# Ethernet_Besturing.net
KiCad netlist of a schematic drawn in EasyEDA
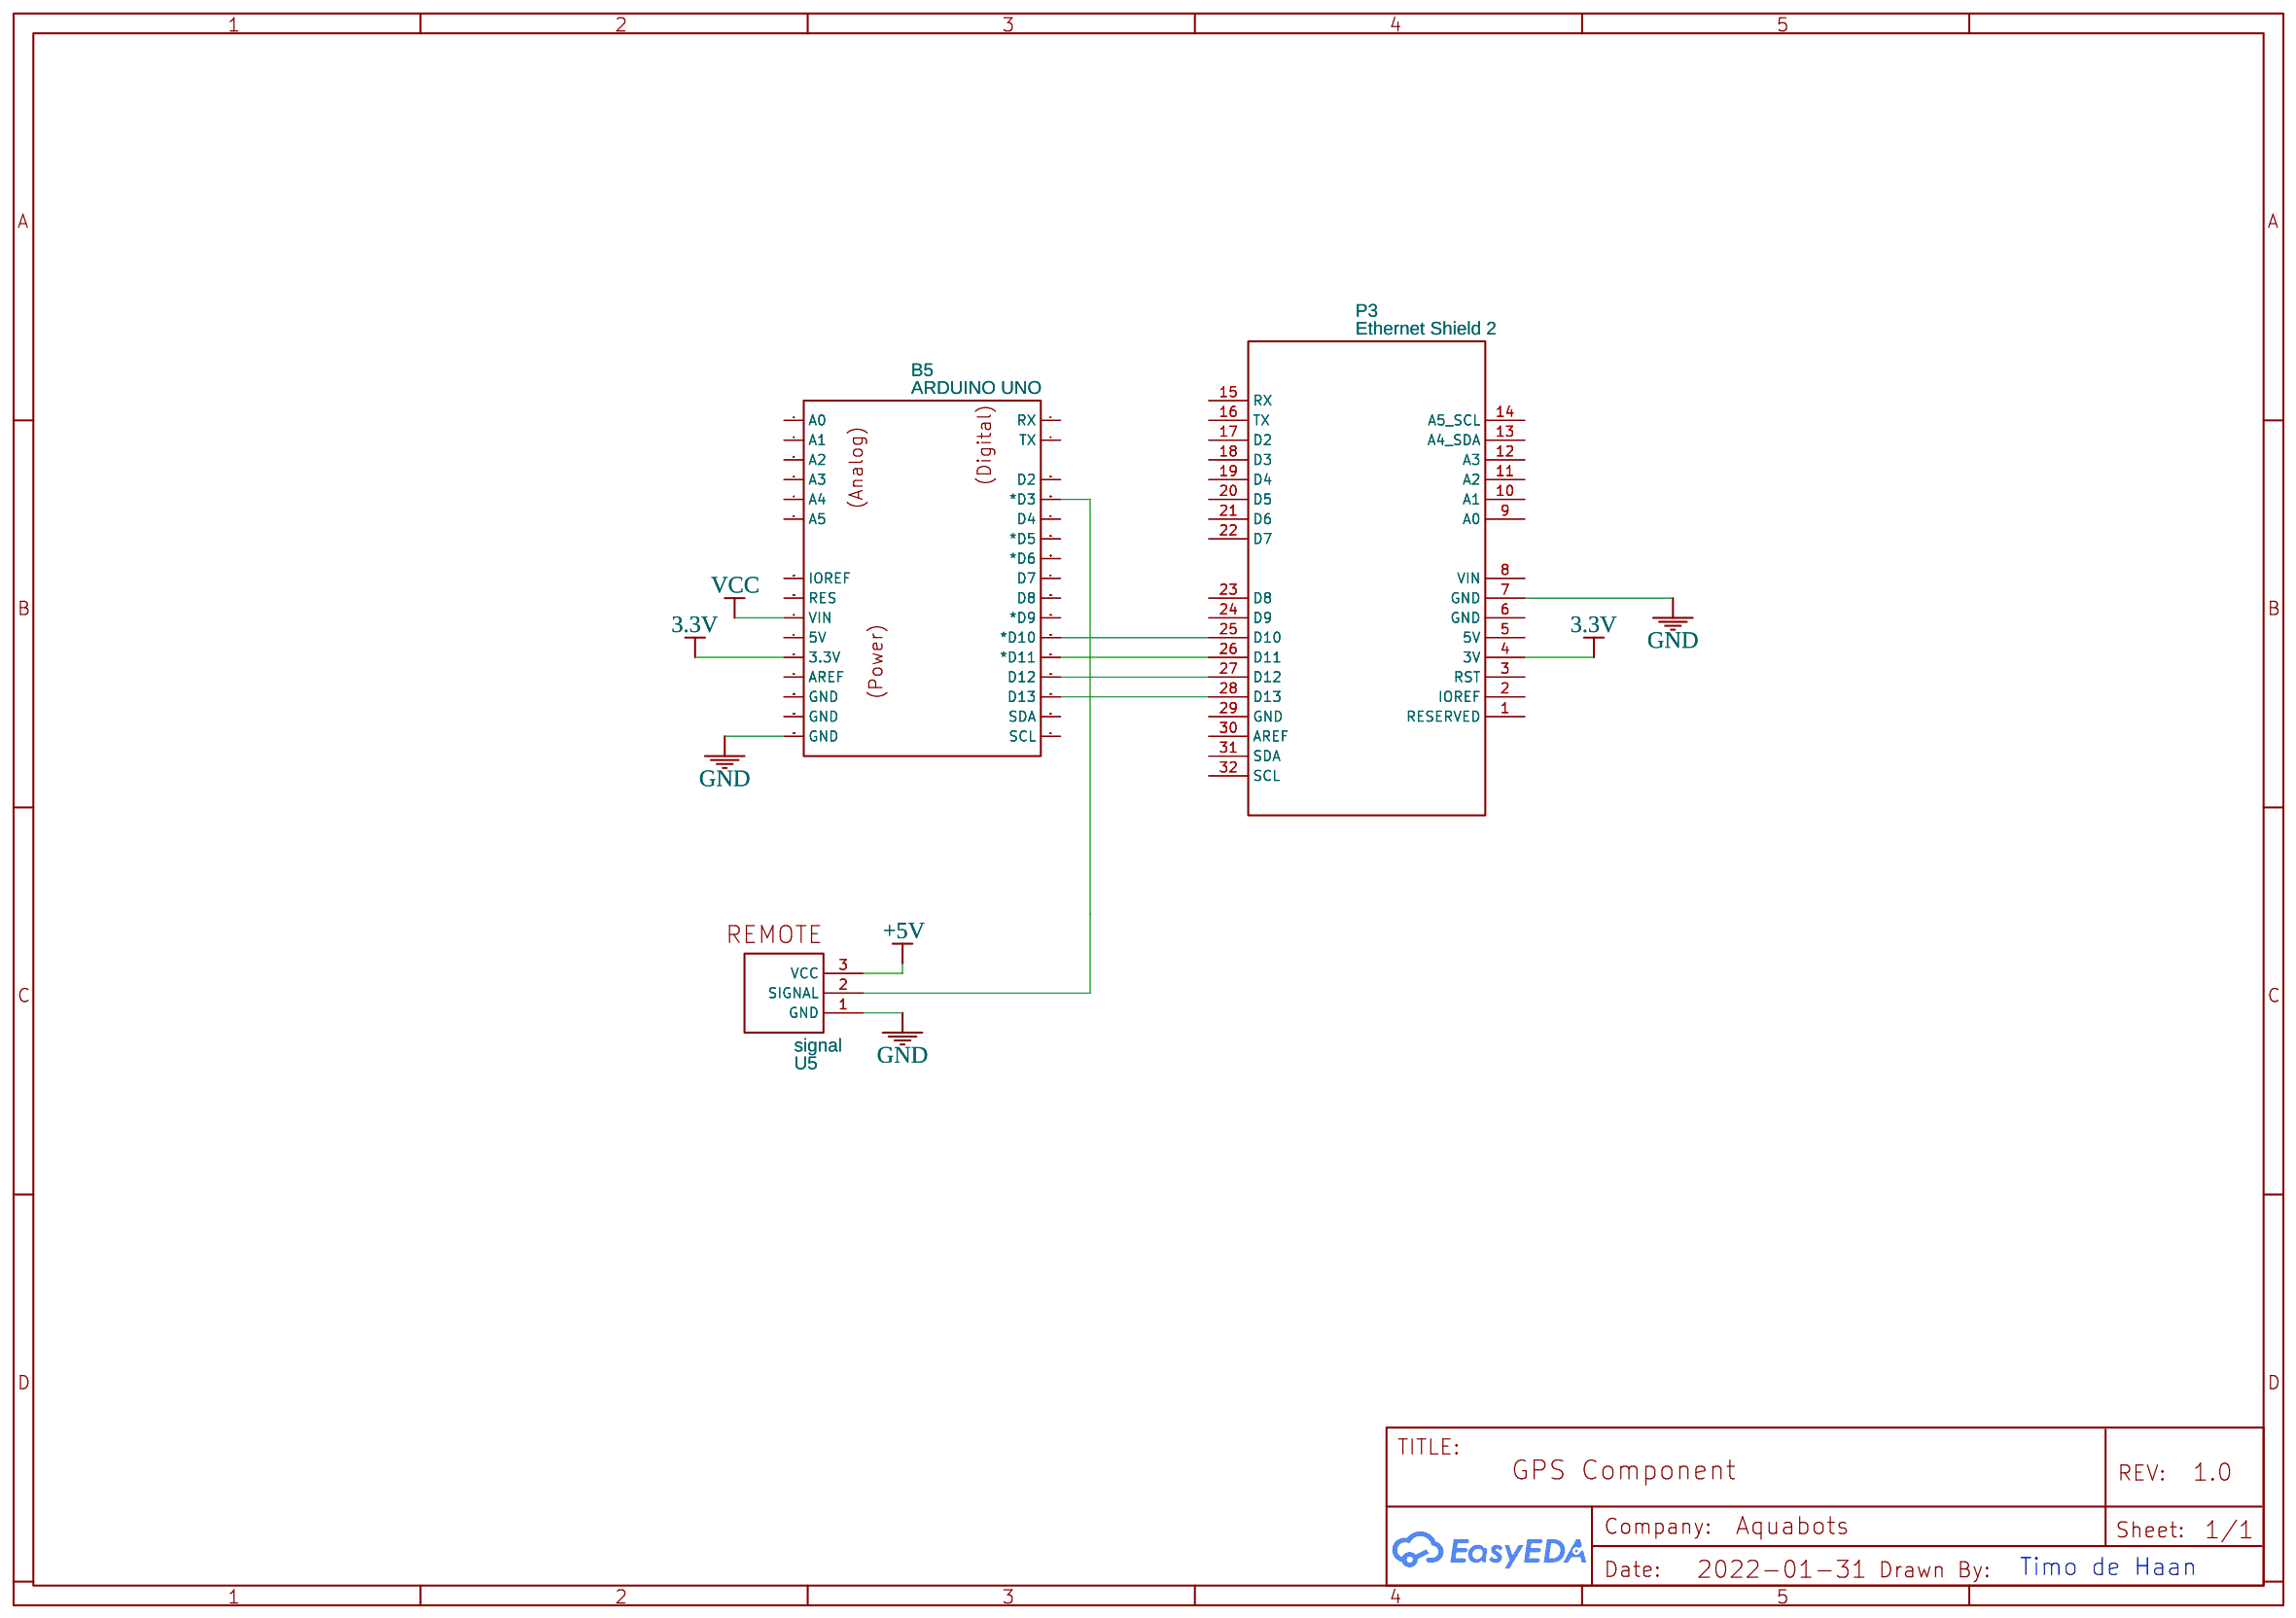
[diagram p0: schematic sheet]

(export (version "E")
  (design (tool "Eeschema 10.0.6"))
  (components
    (comp (ref "B5")
      (value "ARDUINO UNO")
      (fields (field (name "Manufacturer") "?"))
      (libsource (lib "") (part "ARDUINO UNO R3 SHIELD"))
    )
    (comp (ref "P3") (value "Ethernet Shield 2") (libsource (lib "") (part "Ethernet Shield 2")))
    (comp (ref "U5") (value "signal") (libsource (lib "") (part "signal")))
  )
  (nets
    (net (code "1") (name "+5V") (class "Default")
      (node (ref "U5") (pin "3") (pinfunction "VCC_3") (pintype "unspecified"))
    )
    (net (code "2") (name "3.3V") (class "Default")
      (node (ref "B5") (pin "3.3V") (pinfunction "3.3V_3.3V") (pintype "unspecified"))
      (node (ref "P3") (pin "4") (pinfunction "3V_4") (pintype "unspecified"))
    )
    (net (code "3") (name "GND") (class "Default")
      (node (ref "B5") (pin "GND@0") (pinfunction "GND_GND@0") (pintype "unspecified"))
      (node (ref "P3") (pin "7") (pinfunction "GND_7") (pintype "unspecified"))
      (node (ref "U5") (pin "1") (pinfunction "GND_1") (pintype "unspecified"))
    )
    (net (code "4") (name "Net-(B5-*D3)") (class "Default")
      (node (ref "B5") (pin "D3") (pinfunction "*D3_D3") (pintype "unspecified"))
      (node (ref "U5") (pin "2") (pinfunction "SIGNAL_2") (pintype "unspecified"))
    )
    (net (code "5") (name "Net-(B5-*D10)") (class "Default")
      (node (ref "B5") (pin "D10") (pinfunction "*D10_D10") (pintype "unspecified"))
      (node (ref "P3") (pin "25") (pinfunction "D10_25") (pintype "unspecified"))
    )
    (net (code "6") (name "Net-(B5-*D11)") (class "Default")
      (node (ref "B5") (pin "D11") (pinfunction "*D11_D11") (pintype "unspecified"))
      (node (ref "P3") (pin "26") (pinfunction "D11_26") (pintype "unspecified"))
    )
    (net (code "7") (name "Net-(P3-D12)") (class "Default")
      (node (ref "B5") (pin "D12") (pinfunction "D12_D12") (pintype "unspecified"))
      (node (ref "P3") (pin "27") (pinfunction "D12_27") (pintype "unspecified"))
    )
    (net (code "8") (name "Net-(P3-D13)") (class "Default")
      (node (ref "B5") (pin "D13") (pinfunction "D13_D13") (pintype "unspecified"))
      (node (ref "P3") (pin "28") (pinfunction "D13_28") (pintype "unspecified"))
    )
    (net (code "9") (name "VCC") (class "Default")
      (node (ref "B5") (pin "VIN") (pinfunction "VIN_VIN") (pintype "unspecified"))
    )
    (net (code "10") (name "unconnected-(B5-*D5-PadD5)") (class "Default")
      (node (ref "B5") (pin "D5") (pinfunction "*D5_D5") (pintype "unspecified"))
    )
    (net (code "11") (name "unconnected-(B5-*D6-PadD6)") (class "Default")
      (node (ref "B5") (pin "D6") (pinfunction "*D6_D6") (pintype "unspecified"))
    )
    (net (code "12") (name "unconnected-(B5-*D9-PadD9)") (class "Default")
      (node (ref "B5") (pin "D9") (pinfunction "*D9_D9") (pintype "unspecified"))
    )
    (net (code "13") (name "unconnected-(B5-GND-PadGND@1)") (class "Default")
      (node (ref "B5") (pin "GND@1") (pinfunction "GND_GND@1") (pintype "unspecified"))
    )
    (net (code "14") (name "unconnected-(B5-GND-PadGND@2)") (class "Default")
      (node (ref "B5") (pin "GND@2") (pinfunction "GND_GND@2") (pintype "unspecified"))
    )
    (net (code "15") (name "unconnected-(B5-Pad5V)") (class "Default")
      (node (ref "B5") (pin "5V") (pinfunction "5V_5V") (pintype "unspecified"))
    )
    (net (code "16") (name "unconnected-(B5-PadA0)") (class "Default")
      (node (ref "B5") (pin "A0") (pinfunction "A0_A0") (pintype "unspecified"))
    )
    (net (code "17") (name "unconnected-(B5-PadA1)") (class "Default")
      (node (ref "B5") (pin "A1") (pinfunction "A1_A1") (pintype "unspecified"))
    )
    (net (code "18") (name "unconnected-(B5-PadA2)") (class "Default")
      (node (ref "B5") (pin "A2") (pinfunction "A2_A2") (pintype "unspecified"))
    )
    (net (code "19") (name "unconnected-(B5-PadA3)") (class "Default")
      (node (ref "B5") (pin "A3") (pinfunction "A3_A3") (pintype "unspecified"))
    )
    (net (code "20") (name "unconnected-(B5-PadA4)") (class "Default")
      (node (ref "B5") (pin "A4") (pinfunction "A4_A4") (pintype "unspecified"))
    )
    (net (code "21") (name "unconnected-(B5-PadA5)") (class "Default")
      (node (ref "B5") (pin "A5") (pinfunction "A5_A5") (pintype "unspecified"))
    )
    (net (code "22") (name "unconnected-(B5-PadAREF)") (class "Default")
      (node (ref "B5") (pin "AREF") (pinfunction "AREF_AREF") (pintype "unspecified"))
    )
    (net (code "23") (name "unconnected-(B5-PadD2)") (class "Default")
      (node (ref "B5") (pin "D2") (pinfunction "D2_D2") (pintype "unspecified"))
    )
    (net (code "24") (name "unconnected-(B5-PadD4)") (class "Default")
      (node (ref "B5") (pin "D4") (pinfunction "D4_D4") (pintype "unspecified"))
    )
    (net (code "25") (name "unconnected-(B5-PadD7)") (class "Default")
      (node (ref "B5") (pin "D7") (pinfunction "D7_D7") (pintype "unspecified"))
    )
    (net (code "26") (name "unconnected-(B5-PadD8)") (class "Default")
      (node (ref "B5") (pin "D8") (pinfunction "D8_D8") (pintype "unspecified"))
    )
    (net (code "27") (name "unconnected-(B5-PadIOREF)") (class "Default")
      (node (ref "B5") (pin "IOREF") (pinfunction "IOREF_IOREF") (pintype "unspecified"))
    )
    (net (code "28") (name "unconnected-(B5-PadRES)") (class "Default")
      (node (ref "B5") (pin "RES") (pinfunction "RES_RES") (pintype "unspecified"))
    )
    (net (code "29") (name "unconnected-(B5-PadRX)") (class "Default")
      (node (ref "B5") (pin "RX") (pinfunction "RX_RX") (pintype "unspecified"))
    )
    (net (code "30") (name "unconnected-(B5-PadSCL)") (class "Default")
      (node (ref "B5") (pin "SCL") (pinfunction "SCL_SCL") (pintype "unspecified"))
    )
    (net (code "31") (name "unconnected-(B5-PadSDA)") (class "Default")
      (node (ref "B5") (pin "SDA") (pinfunction "SDA_SDA") (pintype "unspecified"))
    )
    (net (code "32") (name "unconnected-(B5-PadTX)") (class "Default")
      (node (ref "B5") (pin "TX") (pinfunction "TX_TX") (pintype "unspecified"))
    )
    (net (code "33") (name "unconnected-(P3-5V-Pad5)") (class "Default")
      (node (ref "P3") (pin "5") (pinfunction "5V_5") (pintype "unspecified"))
    )
    (net (code "34") (name "unconnected-(P3-A0-Pad9)") (class "Default")
      (node (ref "P3") (pin "9") (pinfunction "A0_9") (pintype "unspecified"))
    )
    (net (code "35") (name "unconnected-(P3-A1-Pad10)") (class "Default")
      (node (ref "P3") (pin "10") (pinfunction "A1_10") (pintype "unspecified"))
    )
    (net (code "36") (name "unconnected-(P3-A2-Pad11)") (class "Default")
      (node (ref "P3") (pin "11") (pinfunction "A2_11") (pintype "unspecified"))
    )
    (net (code "37") (name "unconnected-(P3-A3-Pad12)") (class "Default")
      (node (ref "P3") (pin "12") (pinfunction "A3_12") (pintype "unspecified"))
    )
    (net (code "38") (name "unconnected-(P3-A4_SDA-Pad13)") (class "Default")
      (node (ref "P3") (pin "13") (pinfunction "A4_SDA_13") (pintype "unspecified"))
    )
    (net (code "39") (name "unconnected-(P3-A5_SCL-Pad14)") (class "Default")
      (node (ref "P3") (pin "14") (pinfunction "A5_SCL_14") (pintype "unspecified"))
    )
    (net (code "40") (name "unconnected-(P3-AREF-Pad30)") (class "Default")
      (node (ref "P3") (pin "30") (pinfunction "AREF_30") (pintype "unspecified"))
    )
    (net (code "41") (name "unconnected-(P3-D2-Pad17)") (class "Default")
      (node (ref "P3") (pin "17") (pinfunction "D2_17") (pintype "unspecified"))
    )
    (net (code "42") (name "unconnected-(P3-D3-Pad18)") (class "Default")
      (node (ref "P3") (pin "18") (pinfunction "D3_18") (pintype "unspecified"))
    )
    (net (code "43") (name "unconnected-(P3-D4-Pad19)") (class "Default")
      (node (ref "P3") (pin "19") (pinfunction "D4_19") (pintype "unspecified"))
    )
    (net (code "44") (name "unconnected-(P3-D5-Pad20)") (class "Default")
      (node (ref "P3") (pin "20") (pinfunction "D5_20") (pintype "unspecified"))
    )
    (net (code "45") (name "unconnected-(P3-D6-Pad21)") (class "Default")
      (node (ref "P3") (pin "21") (pinfunction "D6_21") (pintype "unspecified"))
    )
    (net (code "46") (name "unconnected-(P3-D7-Pad22)") (class "Default")
      (node (ref "P3") (pin "22") (pinfunction "D7_22") (pintype "unspecified"))
    )
    (net (code "47") (name "unconnected-(P3-D8-Pad23)") (class "Default")
      (node (ref "P3") (pin "23") (pinfunction "D8_23") (pintype "unspecified"))
    )
    (net (code "48") (name "unconnected-(P3-D9-Pad24)") (class "Default")
      (node (ref "P3") (pin "24") (pinfunction "D9_24") (pintype "unspecified"))
    )
    (net (code "49") (name "unconnected-(P3-GND-Pad6)") (class "Default")
      (node (ref "P3") (pin "6") (pinfunction "GND_6") (pintype "unspecified"))
    )
    (net (code "50") (name "unconnected-(P3-GND-Pad29)") (class "Default")
      (node (ref "P3") (pin "29") (pinfunction "GND_29") (pintype "unspecified"))
    )
    (net (code "51") (name "unconnected-(P3-IOREF-Pad2)") (class "Default")
      (node (ref "P3") (pin "2") (pinfunction "IOREF_2") (pintype "unspecified"))
    )
    (net (code "52") (name "unconnected-(P3-RESERVED-Pad1)") (class "Default")
      (node (ref "P3") (pin "1") (pinfunction "RESERVED_1") (pintype "unspecified"))
    )
    (net (code "53") (name "unconnected-(P3-RST-Pad3)") (class "Default")
      (node (ref "P3") (pin "3") (pinfunction "RST_3") (pintype "unspecified"))
    )
    (net (code "54") (name "unconnected-(P3-RX-Pad15)") (class "Default")
      (node (ref "P3") (pin "15") (pinfunction "RX_15") (pintype "unspecified"))
    )
    (net (code "55") (name "unconnected-(P3-SCL-Pad32)") (class "Default")
      (node (ref "P3") (pin "32") (pinfunction "SCL_32") (pintype "unspecified"))
    )
    (net (code "56") (name "unconnected-(P3-SDA-Pad31)") (class "Default")
      (node (ref "P3") (pin "31") (pinfunction "SDA_31") (pintype "unspecified"))
    )
    (net (code "57") (name "unconnected-(P3-TX-Pad16)") (class "Default")
      (node (ref "P3") (pin "16") (pinfunction "TX_16") (pintype "unspecified"))
    )
    (net (code "58") (name "unconnected-(P3-VIN-Pad8)") (class "Default")
      (node (ref "P3") (pin "8") (pinfunction "VIN_8") (pintype "unspecified"))
    )
  )
)
